# openSX70_WIP_NEW_LAYOUT_20171225_V30_man.net
KiCad netlist of a schematic drawn in EAGLE
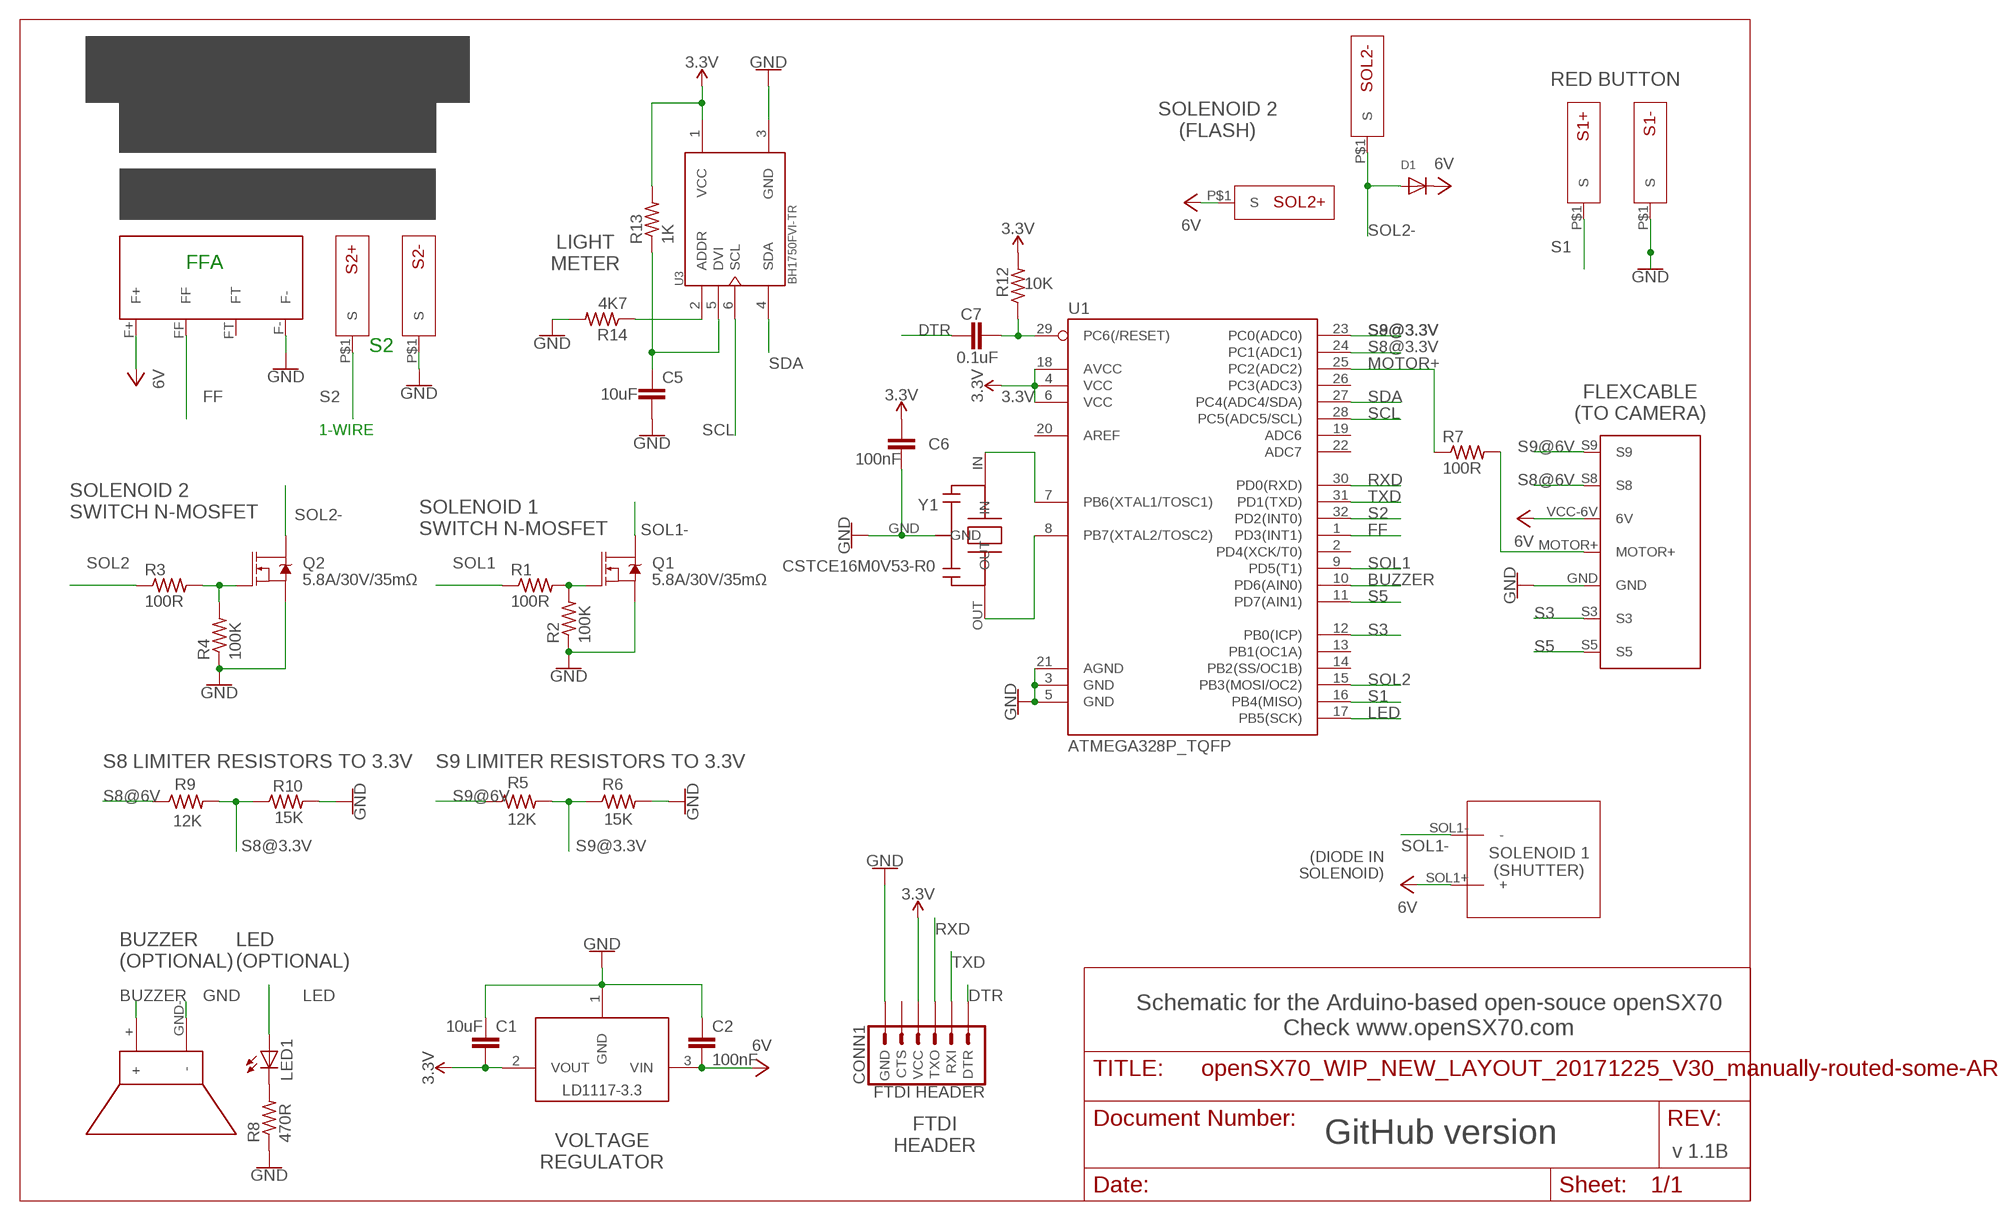
[diagram p0: schematic, sheet 1]

(export (version "E")
  (design (tool "Eeschema 10.0.6"))
  (components
    (comp (ref "BUZZ1")
      (value "CSET8-5G")
      (footprint "eagle-import:CSET8-5G_PACKAGE")
      (libsource (lib "eagle-import") (part "CSET8-5G"))
    )
    (comp (ref "C1")
      (value "10uF")
      (footprint "eagle-import:0603")
      (libsource (lib "eagle-import") (part "10UF-0603-6.3V-20%"))
    )
    (comp (ref "C2")
      (value "100nF")
      (footprint "eagle-import:C0603K")
      (libsource (lib "eagle-import") (part "C-EUC0603K"))
    )
    (comp (ref "C5")
      (value "10uF")
      (footprint "eagle-import:0603")
      (libsource (lib "eagle-import") (part "10UF-0603-6.3V-20%"))
    )
    (comp (ref "C6")
      (value "100nF")
      (footprint "eagle-import:C0805")
      (libsource (lib "eagle-import") (part "resistor_C-EUC0805"))
    )
    (comp (ref "C7")
      (value "0.1uF")
      (footprint "eagle-import:0603")
      (libsource (lib "eagle-import") (part "0.1UF-0603-25V-(+80/-20%)"))
    )
    (comp (ref "CONN1")
      (value "FTDI HEADER")
      (footprint "eagle-import:1X06")
      (libsource (lib "eagle-import") (part "6_PIN_SERIAL_TARGET"))
    )
    (comp (ref "D1")
      (value "DIODESOD-523")
      (footprint "eagle-import:SOD-523")
      (libsource (lib "eagle-import") (part "DIODESOD-523"))
    )
    (comp (ref "LD11173.3V")
      (value "LD1117 3.3V")
      (footprint "eagle-import:SOT223")
      (fields (field (name "MF") "Advanced Monolithic Systems") (field (name "MP") "AMS1117-5.0"))
      (libsource (lib "eagle-import") (part "LD1117-3.3"))
    )
    (comp (ref "LED1")
      (value "LEDCHIPLED_0805")
      (footprint "eagle-import:CHIPLED_0805")
      (libsource (lib "eagle-import") (part "LEDCHIPLED_0805"))
    )
    (comp (ref "Q1")
      (value "5.8A/30V/35mΩ")
      (footprint "eagle-import:SOT23-3")
      (libsource (lib "eagle-import") (part "MOSFET-NCH-AO3404A"))
    )
    (comp (ref "Q2")
      (value "5.8A/30V/35mΩ")
      (footprint "eagle-import:SOT23-3")
      (libsource (lib "eagle-import") (part "MOSFET-NCH-AO3404A"))
    )
    (comp (ref "R1")
      (value "100R")
      (footprint "eagle-import:R0603")
      (libsource (lib "eagle-import") (part "R-US_R0603"))
    )
    (comp (ref "R2")
      (value "100K")
      (footprint "eagle-import:R0603")
      (libsource (lib "eagle-import") (part "R-US_R0603"))
    )
    (comp (ref "R3")
      (value "100R")
      (footprint "eagle-import:R0603")
      (libsource (lib "eagle-import") (part "R-US_R0603"))
    )
    (comp (ref "R4")
      (value "100K")
      (footprint "eagle-import:R0603")
      (libsource (lib "eagle-import") (part "R-US_R0603"))
    )
    (comp (ref "R5")
      (value "12K")
      (footprint "eagle-import:R0603")
      (libsource (lib "eagle-import") (part "R-US_R0603"))
    )
    (comp (ref "R6")
      (value "15K")
      (footprint "eagle-import:R0603")
      (libsource (lib "eagle-import") (part "R-US_R0603"))
    )
    (comp (ref "R7")
      (value "100R")
      (footprint "eagle-import:R0603")
      (libsource (lib "eagle-import") (part "R-US_R0603"))
    )
    (comp (ref "R8")
      (value "470R")
      (footprint "eagle-import:R0603")
      (libsource (lib "eagle-import") (part "R-US_R0603"))
    )
    (comp (ref "R9")
      (value "12K")
      (footprint "eagle-import:R0603")
      (libsource (lib "eagle-import") (part "R-US_R0603"))
    )
    (comp (ref "R10")
      (value "15K")
      (footprint "eagle-import:R0603")
      (libsource (lib "eagle-import") (part "R-US_R0603"))
    )
    (comp (ref "R12")
      (value "10K")
      (footprint "eagle-import:R0603")
      (libsource (lib "eagle-import") (part "R-US_R0603"))
    )
    (comp (ref "R13")
      (value "1K")
      (footprint "eagle-import:R0603")
      (libsource (lib "eagle-import") (part "R-US_R0603"))
    )
    (comp (ref "R14")
      (value "4K7")
      (footprint "eagle-import:R0603")
      (libsource (lib "eagle-import") (part "R-US_R0603"))
    )
    (comp (ref "S1+")
      (value "SX70_S-PAD")
      (footprint "eagle-import:SX70-S-PAD")
      (libsource (lib "eagle-import") (part "SX70_S-PAD"))
    )
    (comp (ref "S1-")
      (value "SX70_S-PAD")
      (footprint "eagle-import:SX70-S-PAD")
      (libsource (lib "eagle-import") (part "SX70_S-PAD"))
    )
    (comp (ref "S2+")
      (value "SX70_S-PAD")
      (footprint "eagle-import:SX70-S-PAD")
      (libsource (lib "eagle-import") (part "SX70_S-PAD"))
    )
    (comp (ref "S2-")
      (value "SX70_S-PAD")
      (footprint "eagle-import:SX70-S-PAD")
      (libsource (lib "eagle-import") (part "SX70_S-PAD"))
    )
    (comp (ref "SOL1")
      (value "SX70-SOLENOID1-2PADS")
      (footprint "eagle-import:SX70-SOLENOID1-2")
      (libsource (lib "eagle-import") (part "SX70-SOLENOID1-2PADS"))
    )
    (comp (ref "SOL2+")
      (value "SX70_S-PAD")
      (footprint "eagle-import:SX70-S-PAD")
      (libsource (lib "eagle-import") (part "SX70_S-PAD"))
    )
    (comp (ref "SOL2-")
      (value "SX70_S-PAD")
      (footprint "eagle-import:SX70-S-PAD")
      (libsource (lib "eagle-import") (part "SX70_S-PAD"))
    )
    (comp (ref "U$1")
      (value "SX70-7-PAD")
      (footprint "eagle-import:SX70-7-PAD")
      (libsource (lib "eagle-import") (part "SX70-7-PAD"))
    )
    (comp (ref "U$2")
      (value "FFA")
      (footprint "eagle-import:FFA-PAD-PACKAGE")
      (libsource (lib "eagle-import") (part "SX70-FFA-PAD"))
    )
    (comp (ref "U1")
      (value "ATMEGA328P_TQFP")
      (footprint "eagle-import:TQFP32-08")
      (libsource (lib "eagle-import") (part "ATMEGA328P_TQFP"))
    )
    (comp (ref "U3")
      (value "BH1750FVI-TR")
      (footprint "eagle-import:SOTFL50P300X75-6N")
      (fields (field (name "MF") "Rohm"))
      (libsource (lib "eagle-import") (part "BH1750FVI-TR"))
    )
    (comp (ref "Y1")
      (value "CSTCE16M0V53-R0")
      (footprint "eagle-import:CFP95P160X100-3N")
      (fields (field (name "MF") "Murata"))
      (libsource (lib "eagle-import") (part "CSTCE16M0V53-R0"))
    )
  )
  (nets
    (net (code "1") (name "/BUZZER") (class "Default")
      (node (ref "BUZZ1") (pin "+") (pinfunction "+_+") (pintype "bidirectional"))
      (node (ref "U1") (pin "10") (pinfunction "PD6(AIN0)_10") (pintype "bidirectional"))
    )
    (net (code "2") (name "/DTR") (class "Default")
      (node (ref "C7") (pin "1") (pinfunction "1_1") (pintype "passive"))
      (node (ref "CONN1") (pin "1") (pinfunction "DTR_1") (pintype "passive"))
    )
    (net (code "3") (name "/FF") (class "Default")
      (node (ref "U$2") (pin "FF") (pinfunction "FF_FF") (pintype "bidirectional"))
      (node (ref "U1") (pin "1") (pinfunction "PD3(INT1)_1") (pintype "bidirectional"))
    )
    (net (code "4") (name "/LED") (class "Default")
      (node (ref "LED1") (pin "A") (pinfunction "A_A") (pintype "passive"))
      (node (ref "U1") (pin "17") (pinfunction "PB5(SCK)_17") (pintype "bidirectional"))
    )
    (net (code "5") (name "/MOTOR+") (class "Default")
      (node (ref "R7") (pin "1") (pinfunction "1_1") (pintype "passive"))
      (node (ref "U1") (pin "25") (pinfunction "PC2(ADC2)_25") (pintype "bidirectional"))
    )
    (net (code "6") (name "/RXD") (class "Default")
      (node (ref "CONN1") (pin "3") (pinfunction "TXO_3") (pintype "passive"))
      (node (ref "U1") (pin "30") (pinfunction "PD0(RXD)_30") (pintype "bidirectional"))
    )
    (net (code "7") (name "/S1") (class "Default")
      (node (ref "S1+") (pin "P$1") (pinfunction "S_P$1") (pintype "bidirectional"))
      (node (ref "U1") (pin "16") (pinfunction "PB4(MISO)_16") (pintype "bidirectional"))
    )
    (net (code "8") (name "/S2") (class "Default")
      (node (ref "S2+") (pin "P$1") (pinfunction "S_P$1") (pintype "bidirectional"))
      (node (ref "U1") (pin "32") (pinfunction "PD2(INT0)_32") (pintype "bidirectional"))
    )
    (net (code "9") (name "/S3") (class "Default")
      (node (ref "U$1") (pin "S3") (pinfunction "S3_S3") (pintype "bidirectional"))
      (node (ref "U1") (pin "12") (pinfunction "PB0(ICP)_12") (pintype "bidirectional"))
    )
    (net (code "10") (name "/S5") (class "Default")
      (node (ref "U$1") (pin "S5") (pinfunction "S5_S5") (pintype "bidirectional"))
      (node (ref "U1") (pin "11") (pinfunction "PD7(AIN1)_11") (pintype "bidirectional"))
    )
    (net (code "11") (name "/S8@3.3V") (class "Default")
      (node (ref "R10") (pin "1") (pinfunction "1_1") (pintype "passive"))
      (node (ref "R9") (pin "2") (pinfunction "2_2") (pintype "passive"))
      (node (ref "U1") (pin "24") (pinfunction "PC1(ADC1)_24") (pintype "bidirectional"))
    )
    (net (code "12") (name "/S8@6V") (class "Default")
      (node (ref "R9") (pin "1") (pinfunction "1_1") (pintype "passive"))
      (node (ref "U$1") (pin "S8") (pinfunction "S8_S8") (pintype "bidirectional"))
    )
    (net (code "13") (name "/S9@3.3V") (class "Default")
      (node (ref "R5") (pin "2") (pinfunction "2_2") (pintype "passive"))
      (node (ref "R6") (pin "1") (pinfunction "1_1") (pintype "passive"))
      (node (ref "U1") (pin "23") (pinfunction "PC0(ADC0)_23") (pintype "bidirectional"))
    )
    (net (code "14") (name "/S9@6V") (class "Default")
      (node (ref "R5") (pin "1") (pinfunction "1_1") (pintype "passive"))
      (node (ref "U$1") (pin "S9") (pinfunction "S9_S9") (pintype "bidirectional"))
    )
    (net (code "15") (name "/SCL") (class "Default")
      (node (ref "U1") (pin "28") (pinfunction "PC5(ADC5/SCL)_28") (pintype "bidirectional"))
      (node (ref "U3") (pin "6") (pinfunction "SCL_6") (pintype "input"))
    )
    (net (code "16") (name "/SDA") (class "Default")
      (node (ref "U1") (pin "27") (pinfunction "PC4(ADC4/SDA)_27") (pintype "bidirectional"))
      (node (ref "U3") (pin "4") (pinfunction "SDA_4") (pintype "bidirectional"))
    )
    (net (code "17") (name "/SOL1") (class "Default")
      (node (ref "R1") (pin "1") (pinfunction "1_1") (pintype "passive"))
      (node (ref "U1") (pin "9") (pinfunction "PD5(T1)_9") (pintype "bidirectional"))
    )
    (net (code "18") (name "/SOL1-") (class "Default")
      (node (ref "Q1") (pin "3") (pinfunction "D_3") (pintype "bidirectional"))
      (node (ref "SOL1") (pin "SOL1-") (pinfunction "-_SOL1-") (pintype "bidirectional"))
    )
    (net (code "19") (name "/SOL2") (class "Default")
      (node (ref "R3") (pin "1") (pinfunction "1_1") (pintype "passive"))
      (node (ref "U1") (pin "15") (pinfunction "PB3(MOSI/OC2)_15") (pintype "bidirectional"))
    )
    (net (code "20") (name "/SOL2-") (class "Default")
      (node (ref "D1") (pin "A") (pinfunction "A_A") (pintype "passive"))
      (node (ref "Q2") (pin "3") (pinfunction "D_3") (pintype "bidirectional"))
      (node (ref "SOL2-") (pin "P$1") (pinfunction "S_P$1") (pintype "bidirectional"))
    )
    (net (code "21") (name "/TXD") (class "Default")
      (node (ref "CONN1") (pin "2") (pinfunction "RXI_2") (pintype "passive"))
      (node (ref "U1") (pin "31") (pinfunction "PD1(TXD)_31") (pintype "bidirectional"))
    )
    (net (code "22") (name "3.3V") (class "Default")
      (node (ref "C1") (pin "2") (pinfunction "2_2") (pintype "passive"))
      (node (ref "C6") (pin "1") (pinfunction "1_1") (pintype "passive"))
      (node (ref "CONN1") (pin "4") (pinfunction "VCC_4") (pintype "passive"))
      (node (ref "LD11173.3V") (pin "2") (pinfunction "VOUT_2") (pintype "bidirectional"))
      (node (ref "R12") (pin "2") (pinfunction "2_2") (pintype "passive"))
      (node (ref "R13") (pin "2") (pinfunction "2_2") (pintype "passive"))
      (node (ref "U1") (pin "18") (pinfunction "AVCC_18") (pintype "bidirectional"))
      (node (ref "U1") (pin "4") (pinfunction "VCC_4") (pintype "bidirectional"))
      (node (ref "U1") (pin "6") (pinfunction "VCC_6") (pintype "bidirectional"))
      (node (ref "U3") (pin "1") (pinfunction "VCC_1") (pintype "power_in"))
    )
    (net (code "23") (name "6V") (class "Default")
      (node (ref "C2") (pin "2") (pinfunction "2_2") (pintype "passive"))
      (node (ref "D1") (pin "K") (pinfunction "C_K") (pintype "passive"))
      (node (ref "LD11173.3V") (pin "3") (pinfunction "VIN_3") (pintype "bidirectional"))
      (node (ref "SOL1") (pin "SOL1+") (pinfunction "+_SOL1+") (pintype "bidirectional"))
      (node (ref "SOL2+") (pin "P$1") (pinfunction "S_P$1") (pintype "bidirectional"))
      (node (ref "U$1") (pin "VCC-6V") (pinfunction "6V_VCC-6V") (pintype "bidirectional"))
      (node (ref "U$2") (pin "F+") (pinfunction "F+_F+") (pintype "bidirectional"))
    )
    (net (code "24") (name "GND") (class "Default")
      (node (ref "BUZZ1") (pin "GND-") (pinfunction "-_GND-") (pintype "bidirectional"))
      (node (ref "C1") (pin "1") (pinfunction "1_1") (pintype "passive"))
      (node (ref "C2") (pin "1") (pinfunction "1_1") (pintype "passive"))
      (node (ref "C5") (pin "2") (pinfunction "2_2") (pintype "passive"))
      (node (ref "C6") (pin "2") (pinfunction "2_2") (pintype "passive"))
      (node (ref "CONN1") (pin "6") (pinfunction "GND_6") (pintype "passive"))
      (node (ref "LD11173.3V") (pin "1") (pinfunction "GND_1") (pintype "bidirectional"))
      (node (ref "Q1") (pin "2") (pinfunction "S_2") (pintype "bidirectional"))
      (node (ref "Q2") (pin "2") (pinfunction "S_2") (pintype "bidirectional"))
      (node (ref "R10") (pin "2") (pinfunction "2_2") (pintype "passive"))
      (node (ref "R14") (pin "2") (pinfunction "2_2") (pintype "passive"))
      (node (ref "R2") (pin "1") (pinfunction "1_1") (pintype "passive"))
      (node (ref "R4") (pin "1") (pinfunction "1_1") (pintype "passive"))
      (node (ref "R6") (pin "2") (pinfunction "2_2") (pintype "passive"))
      (node (ref "R8") (pin "1") (pinfunction "1_1") (pintype "passive"))
      (node (ref "S1-") (pin "P$1") (pinfunction "S_P$1") (pintype "bidirectional"))
      (node (ref "S2-") (pin "P$1") (pinfunction "S_P$1") (pintype "bidirectional"))
      (node (ref "U$1") (pin "GND") (pinfunction "GND_GND") (pintype "bidirectional"))
      (node (ref "U$2") (pin "F-") (pinfunction "F-_F-") (pintype "bidirectional"))
      (node (ref "U1") (pin "21") (pinfunction "AGND_21") (pintype "bidirectional"))
      (node (ref "U1") (pin "3") (pinfunction "GND_3") (pintype "bidirectional"))
      (node (ref "U1") (pin "5") (pinfunction "GND_5") (pintype "bidirectional"))
      (node (ref "U3") (pin "3") (pinfunction "GND_3") (pintype "power_in"))
      (node (ref "Y1") (pin "GND") (pinfunction "GND_GND") (pintype "passive"))
    )
    (net (code "25") (name "Net-(LED1-PadC)") (class "Default")
      (node (ref "LED1") (pin "C") (pinfunction "C_C") (pintype "passive"))
      (node (ref "R8") (pin "2") (pinfunction "2_2") (pintype "passive"))
    )
    (net (code "26") (name "Net-(Q1-G)") (class "Default")
      (node (ref "Q1") (pin "1") (pinfunction "G_1") (pintype "bidirectional"))
      (node (ref "R1") (pin "2") (pinfunction "2_2") (pintype "passive"))
      (node (ref "R2") (pin "2") (pinfunction "2_2") (pintype "passive"))
    )
    (net (code "27") (name "Net-(Q2-G)") (class "Default")
      (node (ref "Q2") (pin "1") (pinfunction "G_1") (pintype "bidirectional"))
      (node (ref "R3") (pin "2") (pinfunction "2_2") (pintype "passive"))
      (node (ref "R4") (pin "2") (pinfunction "2_2") (pintype "passive"))
    )
    (net (code "28") (name "Net-(R7-Pad2)") (class "Default")
      (node (ref "R7") (pin "2") (pinfunction "2_2") (pintype "passive"))
      (node (ref "U$1") (pin "MOTOR+") (pinfunction "MOTOR+_MOTOR+") (pintype "bidirectional"))
    )
    (net (code "29") (name "Net-(U1-PB6(XTAL1{slash}TOSC1))") (class "Default")
      (node (ref "U1") (pin "7") (pinfunction "PB6(XTAL1/TOSC1)_7") (pintype "bidirectional"))
      (node (ref "Y1") (pin "IN") (pinfunction "IN_IN") (pintype "input"))
    )
    (net (code "30") (name "Net-(U1-PB7(XTAL2{slash}TOSC2))") (class "Default")
      (node (ref "U1") (pin "8") (pinfunction "PB7(XTAL2/TOSC2)_8") (pintype "bidirectional"))
      (node (ref "Y1") (pin "OUT") (pinfunction "OUT_OUT") (pintype "output"))
    )
    (net (code "31") (name "Net-(U1-PC6({slash}RESET))") (class "Default")
      (node (ref "C7") (pin "2") (pinfunction "2_2") (pintype "passive"))
      (node (ref "R12") (pin "1") (pinfunction "1_1") (pintype "passive"))
      (node (ref "U1") (pin "29") (pinfunction "PC6(/RESET)_29") (pintype "bidirectional"))
    )
    (net (code "32") (name "Net-(U3-ADDR)") (class "Default")
      (node (ref "R14") (pin "1") (pinfunction "1_1") (pintype "passive"))
      (node (ref "U3") (pin "2") (pinfunction "ADDR_2") (pintype "input"))
    )
    (net (code "33") (name "Net-(U3-DVI)") (class "Default")
      (node (ref "C5") (pin "1") (pinfunction "1_1") (pintype "passive"))
      (node (ref "R13") (pin "1") (pinfunction "1_1") (pintype "passive"))
      (node (ref "U3") (pin "5") (pinfunction "DVI_5") (pintype "input"))
    )
    (net (code "34") (name "unconnected-(CONN1-CTS-Pad5)") (class "Default")
      (node (ref "CONN1") (pin "5") (pinfunction "CTS_5") (pintype "passive"))
    )
    (net (code "35") (name "unconnected-(U$2-PadFT)") (class "Default")
      (node (ref "U$2") (pin "FT") (pinfunction "FT_FT") (pintype "bidirectional"))
    )
    (net (code "36") (name "unconnected-(U1-ADC6-Pad19)") (class "Default")
      (node (ref "U1") (pin "19") (pinfunction "ADC6_19") (pintype "bidirectional"))
    )
    (net (code "37") (name "unconnected-(U1-ADC7-Pad22)") (class "Default")
      (node (ref "U1") (pin "22") (pinfunction "ADC7_22") (pintype "bidirectional"))
    )
    (net (code "38") (name "unconnected-(U1-AREF-Pad20)") (class "Default")
      (node (ref "U1") (pin "20") (pinfunction "AREF_20") (pintype "bidirectional"))
    )
    (net (code "39") (name "unconnected-(U1-PB1(OC1A)-Pad13)") (class "Default")
      (node (ref "U1") (pin "13") (pinfunction "PB1(OC1A)_13") (pintype "bidirectional"))
    )
    (net (code "40") (name "unconnected-(U1-PB2(SS{slash}OC1B)-Pad14)") (class "Default")
      (node (ref "U1") (pin "14") (pinfunction "PB2(SS/OC1B)_14") (pintype "bidirectional"))
    )
    (net (code "41") (name "unconnected-(U1-PC3(ADC3)-Pad26)") (class "Default")
      (node (ref "U1") (pin "26") (pinfunction "PC3(ADC3)_26") (pintype "bidirectional"))
    )
    (net (code "42") (name "unconnected-(U1-PD4(XCK{slash}T0)-Pad2)") (class "Default")
      (node (ref "U1") (pin "2") (pinfunction "PD4(XCK/T0)_2") (pintype "bidirectional"))
    )
  )
)
